# Integrators.net
KiCad netlist of a schematic drawn in Altium Designer
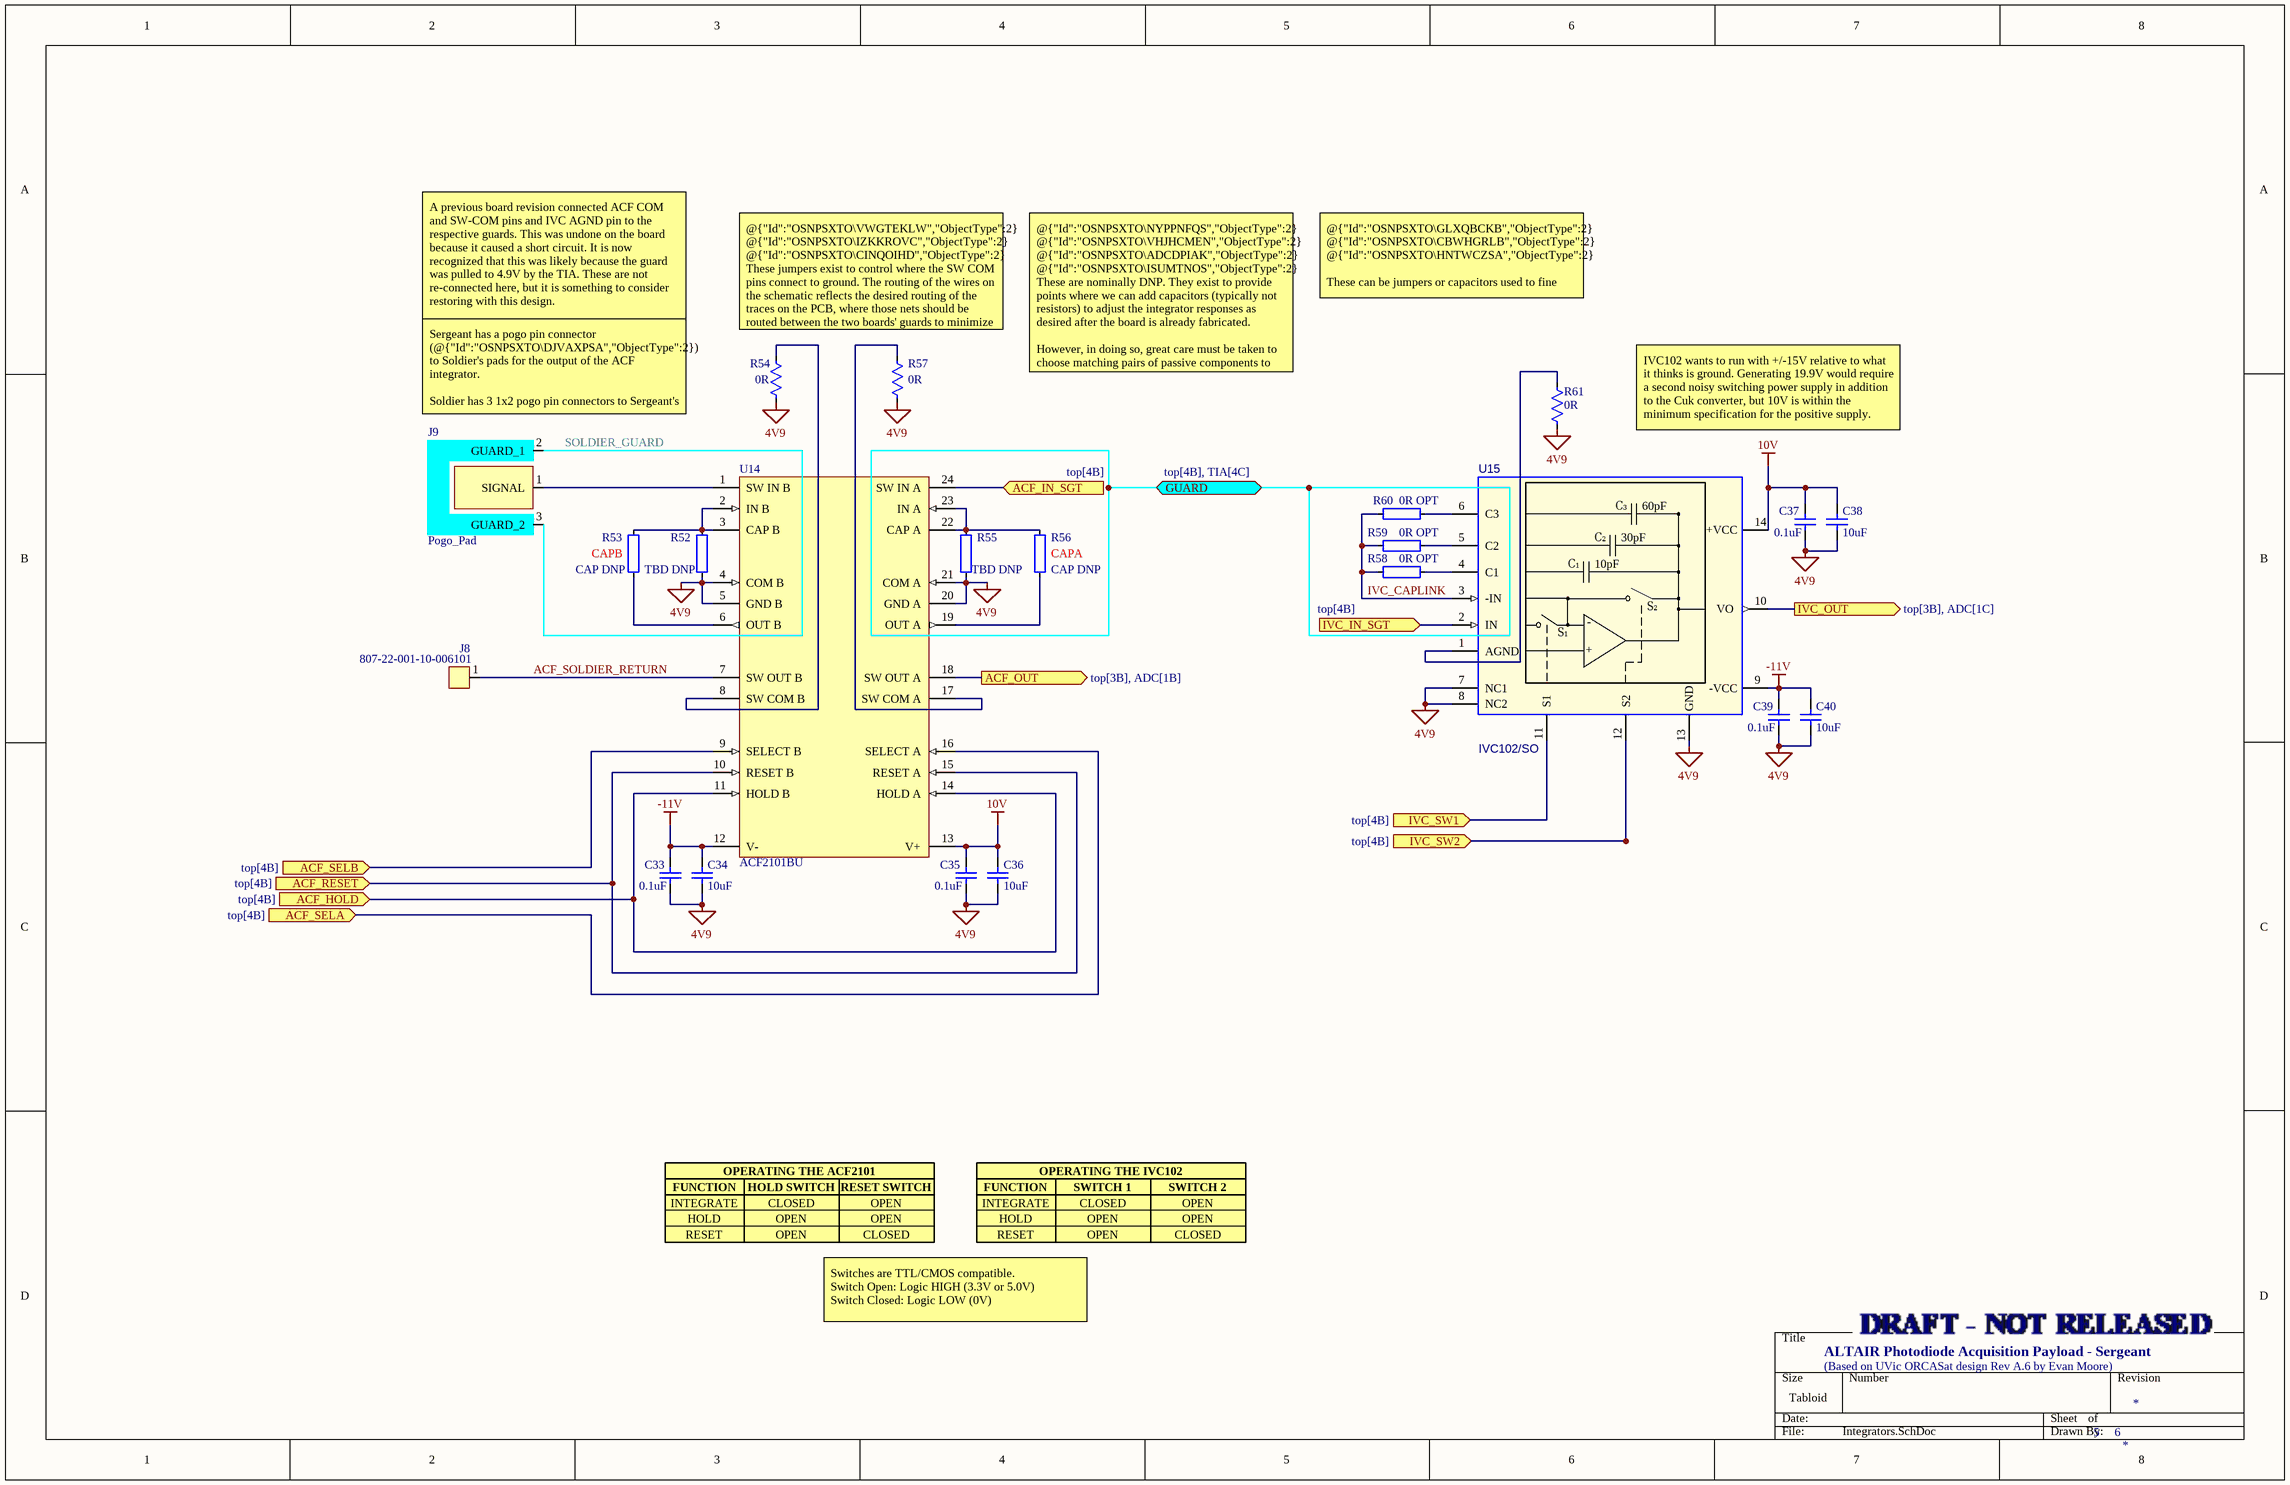
[diagram p0: Integrators.SchDoc]

(export (version "E")
  (design (tool "Eeschema 10.0.6"))
  (components
    (comp (ref "C33")
      (value "0.1uF")
      (footprint "CAP 0603 NON-IPC KEMET X7R")
      (description "Kemet C0603C104K5RACAUTO - Cap Ceramic 0.1uF 50V X7R 10% 0603 125C Paper T/R")
      (fields (field (name "MF") "Kemet") (field (name "MP") "C0603C104K5RACAUTO"))
      (libsource (lib "ALTAIR_PD_Capacitors") (part "CAP"))
    )
    (comp (ref "C34")
      (value "10uF")
      (footprint "CAP 0805 IPC MID DENSITY")
      (description "Murata GRM21BR61E106KA73L - Cap Ceramic 10uF 10% 25V X5R 0805")
      (fields (field (name "MF") "Murata") (field (name "MP") "GRM21BR61E106KA73L"))
      (libsource (lib "ALTAIR_PD_Capacitors") (part "CAP"))
    )
    (comp (ref "C35")
      (value "0.1uF")
      (footprint "CAP 0603 NON-IPC KEMET X7R")
      (description "Kemet C0603C104K5RACAUTO - Cap Ceramic 0.1uF 50V X7R 10% 0603 125C Paper T/R")
      (fields (field (name "MF") "Kemet") (field (name "MP") "C0603C104K5RACAUTO"))
      (libsource (lib "ALTAIR_PD_Capacitors") (part "CAP"))
    )
    (comp (ref "C36")
      (value "10uF")
      (footprint "CAP 0805 IPC MID DENSITY")
      (description "Murata GRM21BR61E106KA73L - Cap Ceramic 10uF 10% 25V X5R 0805")
      (fields (field (name "MF") "Murata") (field (name "MP") "GRM21BR61E106KA73L"))
      (libsource (lib "ALTAIR_PD_Capacitors") (part "CAP"))
    )
    (comp (ref "C37")
      (value "0.1uF")
      (footprint "CAP 0603 NON-IPC KEMET X7R")
      (description "Kemet C0603C104K5RACAUTO - Cap Ceramic 0.1uF 50V X7R 10% 0603 125C Paper T/R")
      (fields (field (name "MF") "Kemet") (field (name "MP") "C0603C104K5RACAUTO"))
      (libsource (lib "ALTAIR_PD_Capacitors") (part "CAP"))
    )
    (comp (ref "C38")
      (value "10uF")
      (footprint "CAP 0805 IPC MID DENSITY")
      (description "Murata GRM21BR61E106KA73L - Cap Ceramic 10uF 10% 25V X5R 0805")
      (fields (field (name "MF") "Murata") (field (name "MP") "GRM21BR61E106KA73L"))
      (libsource (lib "ALTAIR_PD_Capacitors") (part "CAP"))
    )
    (comp (ref "C39")
      (value "0.1uF")
      (footprint "CAP 0603 NON-IPC KEMET X7R")
      (description "Kemet C0603C104K5RACAUTO - Cap Ceramic 0.1uF 50V X7R 10% 0603 125C Paper T/R")
      (fields (field (name "MF") "Kemet") (field (name "MP") "C0603C104K5RACAUTO"))
      (libsource (lib "ALTAIR_PD_Capacitors") (part "CAP"))
    )
    (comp (ref "C40")
      (value "10uF")
      (footprint "CAP 0805 IPC MID DENSITY")
      (description "Murata GRM21BR61E106KA73L - Cap Ceramic 10uF 10% 25V X5R 0805")
      (fields (field (name "MF") "Murata") (field (name "MP") "GRM21BR61E106KA73L"))
      (libsource (lib "ALTAIR_PD_Capacitors") (part "CAP"))
    )
    (comp (ref "J8")
      (value "807-22-001-10-006101")
      (footprint "POGO PIN 807-22-001-10-006101")
      (description "Mill-Max Individual Insulated Pin 5.99mm Initial Height")
      (fields (field (name "MF") "Mill-Max"))
      (libsource (lib "ALTAIR_PD_Pogo") (part "807-22-001-10-006101"))
    )
    (comp (ref "J9")
      (value "Pogo_Pad")
      (footprint "POGO PAD SERGEANT")
      (description "Pad for Pogo Pins with Guard")
      (libsource (lib "ALTAIR_PD_Pogo") (part "Pogo_Pad"))
    )
    (comp (ref "R52")
      (value "TBD DNP")
      (footprint "RES 0402 IPC LOW DENSITY")
      (description "Yageo RC0402JR-070RL - Res 0 Ohms 1/16W SMD 0402")
      (fields (field (name "MF") "YAGEO") (field (name "MP") "RC0402JR-070RL"))
      (libsource (lib "ALTAIR_PD_Resistors") (part "IMPEDANCE"))
    )
    (comp (ref "R53")
      (value "CAP DNP")
      (footprint "RES 0402 IPC LOW DENSITY")
      (description "Yageo RC0402JR-070RL - Res 0 Ohms 1/16W SMD 0402")
      (fields (field (name "MF") "YAGEO") (field (name "MP") "RC0402JR-070RL"))
      (libsource (lib "ALTAIR_PD_Resistors") (part "IMPEDANCE"))
    )
    (comp (ref "R54")
      (value "0R")
      (footprint "RES 0402 IPC MID DENSITY")
      (description "Yageo RC0402JR-070RL - Res 0 Ohms 1/16W SMD 0402")
      (fields (field (name "MF") "YAGEO") (field (name "MP") "RC0402JR-070RL"))
      (libsource (lib "ALTAIR_PD_Resistors") (part "RES"))
    )
    (comp (ref "R55")
      (value "TBD DNP")
      (footprint "RES 0402 IPC LOW DENSITY")
      (description "Yageo RC0402JR-070RL - Res 0 Ohms 1/16W SMD 0402")
      (fields (field (name "MF") "YAGEO") (field (name "MP") "RC0402JR-070RL"))
      (libsource (lib "ALTAIR_PD_Resistors") (part "IMPEDANCE"))
    )
    (comp (ref "R56")
      (value "CAP DNP")
      (footprint "RES 0402 IPC LOW DENSITY")
      (description "Yageo RC0402JR-070RL - Res 0 Ohms 1/16W SMD 0402")
      (fields (field (name "MF") "YAGEO") (field (name "MP") "RC0402JR-070RL"))
      (libsource (lib "ALTAIR_PD_Resistors") (part "IMPEDANCE"))
    )
    (comp (ref "R57")
      (value "0R")
      (footprint "RES 0402 IPC MID DENSITY")
      (description "Yageo RC0402JR-070RL - Res 0 Ohms 1/16W SMD 0402")
      (fields (field (name "MF") "YAGEO") (field (name "MP") "RC0402JR-070RL"))
      (libsource (lib "ALTAIR_PD_Resistors") (part "RES"))
    )
    (comp (ref "R58")
      (value "0R OPT")
      (footprint "RES 0402 IPC LOW DENSITY")
      (description "Yageo RC0402JR-070RL - Res 0 Ohms 1/16W SMD 0402")
      (fields (field (name "MF") "YAGEO") (field (name "MP") "RC0402JR-070RL"))
      (libsource (lib "ALTAIR_PD_Resistors") (part "IMPEDANCE"))
    )
    (comp (ref "R59")
      (value "0R OPT")
      (footprint "RES 0402 IPC LOW DENSITY")
      (description "Yageo RC0402JR-070RL - Res 0 Ohms 1/16W SMD 0402")
      (fields (field (name "MF") "YAGEO") (field (name "MP") "RC0402JR-070RL"))
      (libsource (lib "ALTAIR_PD_Resistors") (part "IMPEDANCE"))
    )
    (comp (ref "R60")
      (value "0R OPT")
      (footprint "RES 0402 IPC LOW DENSITY")
      (description "Yageo RC0402JR-070RL - Res 0 Ohms 1/16W SMD 0402")
      (fields (field (name "MF") "YAGEO") (field (name "MP") "RC0402JR-070RL"))
      (libsource (lib "ALTAIR_PD_Resistors") (part "IMPEDANCE"))
    )
    (comp (ref "R61")
      (value "0R")
      (footprint "RES 0402 IPC MID DENSITY")
      (description "Yageo RC0402JR-070RL - Res 0 Ohms 1/16W SMD 0402")
      (fields (field (name "MF") "YAGEO") (field (name "MP") "RC0402JR-070RL"))
      (libsource (lib "ALTAIR_PD_Resistors") (part "RES"))
    )
    (comp (ref "U14")
      (value "ACF2101BU")
      (footprint "ALTAIR_PD_SOIC:24-SOIC 7.6MM WIDE LOW DENSITY")
      (fields (field (name "MF") "Texas Instruments"))
      (libsource (lib "ALTAIR_PD_Amplifiers") (part "ACF2101BU"))
    )
    (comp (ref "U15")
      (value "IVC102/SO")
      (footprint "14-SOIC 4MM WIDE LOW DENSITY")
      (description "Precision Switched Integrator Transimpedance Amplifier")
      (fields (field (name "MF") "Texas Instruments") (field (name "MP") "IVC102U"))
      (libsource (lib "ALTAIR_PD_Amplifiers") (part "IVC102/SO_5"))
    )
  )
  (nets
    (net (code "1") (name "-11V") (class "Default")
      (node (ref "C33") (pin "2") (pinfunction "2_2") (pintype "passive"))
      (node (ref "C34") (pin "2") (pinfunction "2_2") (pintype "passive"))
      (node (ref "C39") (pin "2") (pinfunction "2_2") (pintype "passive"))
      (node (ref "C40") (pin "2") (pinfunction "2_2") (pintype "passive"))
      (node (ref "U14") (pin "12") (pinfunction "V-_12") (pintype "power_in"))
      (node (ref "U15") (pin "9") (pinfunction "-VCC_9") (pintype "power_in"))
    )
    (net (code "2") (name "/ACF_HOLD") (class "Default")
      (node (ref "U14") (pin "11") (pinfunction "HOLD_B_11") (pintype "input"))
      (node (ref "U14") (pin "14") (pinfunction "HOLD_A_14") (pintype "input"))
    )
    (net (code "3") (name "/ACF_IN_SGT") (class "Default")
      (node (ref "U14") (pin "24") (pinfunction "SW_IN_A_24") (pintype "passive"))
    )
    (net (code "4") (name "/ACF_OUT") (class "Default")
      (node (ref "U14") (pin "18") (pinfunction "SW_OUT_A_18") (pintype "passive"))
    )
    (net (code "5") (name "/ACF_RESET") (class "Default")
      (node (ref "U14") (pin "10") (pinfunction "RESET_B_10") (pintype "input"))
      (node (ref "U14") (pin "15") (pinfunction "RESET_A_15") (pintype "input"))
    )
    (net (code "6") (name "/ACF_SELA") (class "Default")
      (node (ref "U14") (pin "16") (pinfunction "SELECT_A_16") (pintype "input"))
    )
    (net (code "7") (name "/ACF_SELB") (class "Default")
      (node (ref "U14") (pin "9") (pinfunction "SELECT_B_9") (pintype "input"))
    )
    (net (code "8") (name "/ACF_SOLDIER_RETURN") (class "Default")
      (node (ref "J8") (pin "1") (pinfunction "1_1") (pintype "passive"))
      (node (ref "U14") (pin "7") (pinfunction "SW_OUT_B_7") (pintype "passive"))
    )
    (net (code "10") (name "/IVC_CAPLINK") (class "Default")
      (node (ref "R58") (pin "1") (pinfunction "1_1") (pintype "passive"))
      (node (ref "R59") (pin "1") (pinfunction "1_1") (pintype "passive"))
      (node (ref "R60") (pin "1") (pinfunction "1_1") (pintype "passive"))
      (node (ref "U15") (pin "3") (pinfunction "-IN_3") (pintype "input"))
    )
    (net (code "11") (name "/IVC_IN_SGT") (class "Default")
      (node (ref "U15") (pin "2") (pinfunction "IN_2") (pintype "input"))
    )
    (net (code "12") (name "/IVC_OUT") (class "Default")
      (node (ref "U15") (pin "10") (pinfunction "VO_10") (pintype "output"))
    )
    (net (code "13") (name "/IVC_SW1") (class "Default")
      (node (ref "U15") (pin "11") (pinfunction "S1_11") (pintype "passive"))
    )
    (net (code "14") (name "/IVC_SW2") (class "Default")
      (node (ref "U15") (pin "12") (pinfunction "S2_12") (pintype "passive"))
    )
    (net (code "15") (name "/SOLDIER_GUARD") (class "Default")
      (node (ref "J9") (pin "2") (pinfunction "GUARD_1_2") (pintype "passive"))
      (node (ref "J9") (pin "3") (pinfunction "GUARD_2_3") (pintype "passive"))
    )
    (net (code "16") (name "4V9") (class "Default")
      (node (ref "C33") (pin "1") (pinfunction "1_1") (pintype "passive"))
      (node (ref "C34") (pin "1") (pinfunction "1_1") (pintype "passive"))
      (node (ref "C35") (pin "1") (pinfunction "1_1") (pintype "passive"))
      (node (ref "C36") (pin "1") (pinfunction "1_1") (pintype "passive"))
      (node (ref "C37") (pin "1") (pinfunction "1_1") (pintype "passive"))
      (node (ref "C38") (pin "1") (pinfunction "1_1") (pintype "passive"))
      (node (ref "C39") (pin "1") (pinfunction "1_1") (pintype "passive"))
      (node (ref "C40") (pin "1") (pinfunction "1_1") (pintype "passive"))
      (node (ref "R52") (pin "1") (pinfunction "1_1") (pintype "passive"))
      (node (ref "R54") (pin "2") (pinfunction "2_2") (pintype "passive"))
      (node (ref "R55") (pin "1") (pinfunction "1_1") (pintype "passive"))
      (node (ref "R57") (pin "2") (pinfunction "2_2") (pintype "passive"))
      (node (ref "R61") (pin "2") (pinfunction "2_2") (pintype "passive"))
      (node (ref "U14") (pin "20") (pinfunction "GND_A_20") (pintype "power_in"))
      (node (ref "U14") (pin "21") (pinfunction "COM_A_21") (pintype "input"))
      (node (ref "U14") (pin "4") (pinfunction "COM_B_4") (pintype "input"))
      (node (ref "U14") (pin "5") (pinfunction "GND_B_5") (pintype "power_in"))
      (node (ref "U15") (pin "13") (pinfunction "GND_13") (pintype "power_in"))
      (node (ref "U15") (pin "7") (pinfunction "NC1_7") (pintype "passive"))
      (node (ref "U15") (pin "8") (pinfunction "NC2_8") (pintype "passive"))
    )
    (net (code "17") (name "10V") (class "Default")
      (node (ref "C35") (pin "2") (pinfunction "2_2") (pintype "passive"))
      (node (ref "C36") (pin "2") (pinfunction "2_2") (pintype "passive"))
      (node (ref "C37") (pin "2") (pinfunction "2_2") (pintype "passive"))
      (node (ref "C38") (pin "2") (pinfunction "2_2") (pintype "passive"))
      (node (ref "U14") (pin "13") (pinfunction "V+_13") (pintype "power_in"))
      (node (ref "U15") (pin "14") (pinfunction "+VCC_14") (pintype "power_in"))
    )
    (net (code "18") (name "Net-(J9-SIGNAL)") (class "Default")
      (node (ref "J9") (pin "1") (pinfunction "SIGNAL_1") (pintype "passive"))
      (node (ref "U14") (pin "1") (pinfunction "SW_IN_B_1") (pintype "passive"))
    )
    (net (code "19") (name "Net-(U14-CAP_A)") (class "Default")
      (node (ref "R55") (pin "2") (pinfunction "2_2") (pintype "passive"))
      (node (ref "R56") (pin "2") (pinfunction "2_2") (pintype "passive"))
      (node (ref "U14") (pin "22") (pinfunction "CAP_A_22") (pintype "passive"))
      (node (ref "U14") (pin "23") (pinfunction "IN_A_23") (pintype "input"))
    )
    (net (code "20") (name "Net-(U14-CAP_B)") (class "Default")
      (node (ref "R52") (pin "2") (pinfunction "2_2") (pintype "passive"))
      (node (ref "R53") (pin "2") (pinfunction "2_2") (pintype "passive"))
      (node (ref "U14") (pin "2") (pinfunction "IN_B_2") (pintype "input"))
      (node (ref "U14") (pin "3") (pinfunction "CAP_B_3") (pintype "passive"))
    )
    (net (code "21") (name "Net-(U14-OUT_A)") (class "Default")
      (node (ref "R56") (pin "1") (pinfunction "1_1") (pintype "passive"))
      (node (ref "U14") (pin "19") (pinfunction "OUT_A_19") (pintype "output"))
    )
    (net (code "22") (name "Net-(U14-OUT_B)") (class "Default")
      (node (ref "R53") (pin "1") (pinfunction "1_1") (pintype "passive"))
      (node (ref "U14") (pin "6") (pinfunction "OUT_B_6") (pintype "output"))
    )
    (net (code "23") (name "Net-(U14-SW_COM_A)") (class "Default")
      (node (ref "R57") (pin "1") (pinfunction "1_1") (pintype "passive"))
      (node (ref "U14") (pin "17") (pinfunction "SW_COM_A_17") (pintype "passive"))
    )
    (net (code "24") (name "Net-(U14-SW_COM_B)") (class "Default")
      (node (ref "R54") (pin "1") (pinfunction "1_1") (pintype "passive"))
      (node (ref "U14") (pin "8") (pinfunction "SW_COM_B_8") (pintype "passive"))
    )
    (net (code "25") (name "Net-(U15-AGND)") (class "Default")
      (node (ref "R61") (pin "1") (pinfunction "1_1") (pintype "passive"))
      (node (ref "U15") (pin "1") (pinfunction "AGND_1") (pintype "power_in"))
    )
    (net (code "26") (name "Net-(U15-C1)") (class "Default")
      (node (ref "R58") (pin "2") (pinfunction "2_2") (pintype "passive"))
      (node (ref "U15") (pin "4") (pinfunction "C1_4") (pintype "passive"))
    )
    (net (code "27") (name "Net-(U15-C2)") (class "Default")
      (node (ref "R59") (pin "2") (pinfunction "2_2") (pintype "passive"))
      (node (ref "U15") (pin "5") (pinfunction "C2_5") (pintype "passive"))
    )
    (net (code "28") (name "Net-(U15-C3)") (class "Default")
      (node (ref "R60") (pin "2") (pinfunction "2_2") (pintype "passive"))
      (node (ref "U15") (pin "6") (pinfunction "C3_6") (pintype "passive"))
    )
  )
)
